# SRAM.net
KiCad netlist of a schematic drawn in Altium Designer
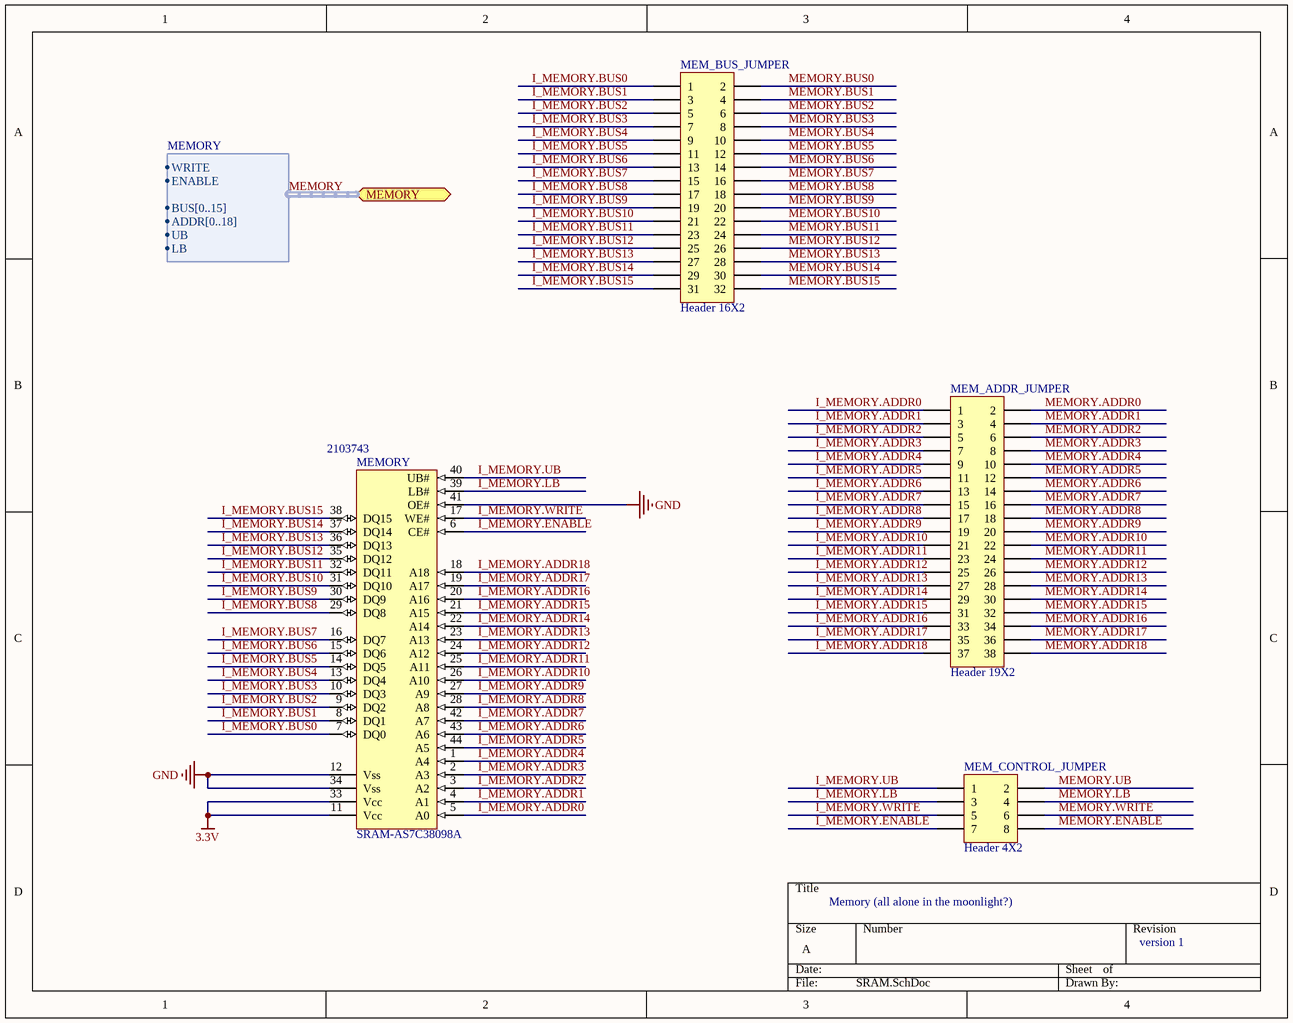
[diagram p0: SRAM.SchDoc]

(export (version "E")
  (design (tool "Eeschema 10.0.6"))
  (components
    (comp (ref "MEMORY")
      (value "SRAM-AS7C38098A")
      (footprint "sram-footprint:AS7C38098A-10TIN")
      (description "ALLIANCE MEMORY - AS7C38098A-10TIN - SRAM, 8MBIT, 512KX16, 3.3V, 44TSOPII")
      (fields
        (field (name "SUPPLIER PART NUMBER 1") "2103743")
        (field (name "MANUFACTURER") "ALLIANCE MEMORY")
        (field (name "MANUFACTURER PART NUMBER") "AS7C38098A-10TIN")
      )
      (libsource (lib "sram-component") (part "memchip-AS7C38098A"))
    )
    (comp (ref "MEM_ADDR_JUMPER")
      (value "Header 19X2")
      (footprint "HDR2X19")
      (description "Header, 19-Pin, Dual row")
      (fields (field (name "PUBLISHER") "Altium Limited"))
      (libsource (lib "Miscellaneous Connectors") (part "Header 19X2"))
    )
    (comp (ref "MEM_BUS_JUMPER")
      (value "Header 16X2")
      (footprint "HDR2X16")
      (description "Header, 16-Pin, Dual row")
      (fields (field (name "PUBLISHER") "Altium Limited"))
      (libsource (lib "Miscellaneous Connectors") (part "Header 16X2"))
    )
    (comp (ref "MEM_CONTROL_JUMPER")
      (value "Header 4X2")
      (footprint "HDR2X4")
      (description "Header, 4-Pin, Dual row")
      (fields (field (name "PUBLISHER") "Altium Limited"))
      (libsource (lib "Miscellaneous Connectors") (part "Header 4X2"))
    )
  )
  (nets
    (net (code "2") (name "/I_MEMORY.ADDR0") (class "Default")
      (node (ref "MEMORY") (pin "5") (pinfunction "A0_5") (pintype "input"))
      (node (ref "MEM_ADDR_JUMPER") (pin "1") (pinfunction "1_1") (pintype "passive"))
    )
    (net (code "3") (name "/I_MEMORY.ADDR1") (class "Default")
      (node (ref "MEMORY") (pin "4") (pinfunction "A1_4") (pintype "input"))
      (node (ref "MEM_ADDR_JUMPER") (pin "3") (pinfunction "3_3") (pintype "passive"))
    )
    (net (code "4") (name "/I_MEMORY.ADDR2") (class "Default")
      (node (ref "MEMORY") (pin "3") (pinfunction "A2_3") (pintype "input"))
      (node (ref "MEM_ADDR_JUMPER") (pin "5") (pinfunction "5_5") (pintype "passive"))
    )
    (net (code "5") (name "/I_MEMORY.ADDR3") (class "Default")
      (node (ref "MEMORY") (pin "2") (pinfunction "A3_2") (pintype "input"))
      (node (ref "MEM_ADDR_JUMPER") (pin "7") (pinfunction "7_7") (pintype "passive"))
    )
    (net (code "6") (name "/I_MEMORY.ADDR4") (class "Default")
      (node (ref "MEMORY") (pin "1") (pinfunction "A4_1") (pintype "input"))
      (node (ref "MEM_ADDR_JUMPER") (pin "9") (pinfunction "9_9") (pintype "passive"))
    )
    (net (code "7") (name "/I_MEMORY.ADDR5") (class "Default")
      (node (ref "MEMORY") (pin "44") (pinfunction "A5_44") (pintype "input"))
      (node (ref "MEM_ADDR_JUMPER") (pin "11") (pinfunction "11_11") (pintype "passive"))
    )
    (net (code "8") (name "/I_MEMORY.ADDR6") (class "Default")
      (node (ref "MEMORY") (pin "43") (pinfunction "A6_43") (pintype "input"))
      (node (ref "MEM_ADDR_JUMPER") (pin "13") (pinfunction "13_13") (pintype "passive"))
    )
    (net (code "9") (name "/I_MEMORY.ADDR7") (class "Default")
      (node (ref "MEMORY") (pin "42") (pinfunction "A7_42") (pintype "input"))
      (node (ref "MEM_ADDR_JUMPER") (pin "15") (pinfunction "15_15") (pintype "passive"))
    )
    (net (code "10") (name "/I_MEMORY.ADDR8") (class "Default")
      (node (ref "MEMORY") (pin "28") (pinfunction "A8_28") (pintype "input"))
      (node (ref "MEM_ADDR_JUMPER") (pin "17") (pinfunction "17_17") (pintype "passive"))
    )
    (net (code "11") (name "/I_MEMORY.ADDR9") (class "Default")
      (node (ref "MEMORY") (pin "27") (pinfunction "A9_27") (pintype "input"))
      (node (ref "MEM_ADDR_JUMPER") (pin "19") (pinfunction "19_19") (pintype "passive"))
    )
    (net (code "12") (name "/I_MEMORY.ADDR10") (class "Default")
      (node (ref "MEMORY") (pin "26") (pinfunction "A10_26") (pintype "input"))
      (node (ref "MEM_ADDR_JUMPER") (pin "21") (pinfunction "21_21") (pintype "passive"))
    )
    (net (code "13") (name "/I_MEMORY.ADDR11") (class "Default")
      (node (ref "MEMORY") (pin "25") (pinfunction "A11_25") (pintype "input"))
      (node (ref "MEM_ADDR_JUMPER") (pin "23") (pinfunction "23_23") (pintype "passive"))
    )
    (net (code "14") (name "/I_MEMORY.ADDR12") (class "Default")
      (node (ref "MEMORY") (pin "24") (pinfunction "A12_24") (pintype "input"))
      (node (ref "MEM_ADDR_JUMPER") (pin "25") (pinfunction "25_25") (pintype "passive"))
    )
    (net (code "15") (name "/I_MEMORY.ADDR13") (class "Default")
      (node (ref "MEMORY") (pin "23") (pinfunction "A13_23") (pintype "input"))
      (node (ref "MEM_ADDR_JUMPER") (pin "27") (pinfunction "27_27") (pintype "passive"))
    )
    (net (code "16") (name "/I_MEMORY.ADDR14") (class "Default")
      (node (ref "MEMORY") (pin "22") (pinfunction "A14_22") (pintype "input"))
      (node (ref "MEM_ADDR_JUMPER") (pin "29") (pinfunction "29_29") (pintype "passive"))
    )
    (net (code "17") (name "/I_MEMORY.ADDR15") (class "Default")
      (node (ref "MEMORY") (pin "21") (pinfunction "A15_21") (pintype "input"))
      (node (ref "MEM_ADDR_JUMPER") (pin "31") (pinfunction "31_31") (pintype "passive"))
    )
    (net (code "18") (name "/I_MEMORY.ADDR16") (class "Default")
      (node (ref "MEMORY") (pin "20") (pinfunction "A16_20") (pintype "input"))
      (node (ref "MEM_ADDR_JUMPER") (pin "33") (pinfunction "33_33") (pintype "passive"))
    )
    (net (code "19") (name "/I_MEMORY.ADDR17") (class "Default")
      (node (ref "MEMORY") (pin "19") (pinfunction "A17_19") (pintype "input"))
      (node (ref "MEM_ADDR_JUMPER") (pin "35") (pinfunction "35_35") (pintype "passive"))
    )
    (net (code "20") (name "/I_MEMORY.ADDR18") (class "Default")
      (node (ref "MEMORY") (pin "18") (pinfunction "A18_18") (pintype "input"))
      (node (ref "MEM_ADDR_JUMPER") (pin "37") (pinfunction "37_37") (pintype "passive"))
    )
    (net (code "21") (name "/I_MEMORY.BUS0") (class "Default")
      (node (ref "MEMORY") (pin "7") (pinfunction "DQ0_7") (pintype "bidirectional"))
      (node (ref "MEM_BUS_JUMPER") (pin "1") (pinfunction "1_1") (pintype "passive"))
    )
    (net (code "22") (name "/I_MEMORY.BUS1") (class "Default")
      (node (ref "MEMORY") (pin "8") (pinfunction "DQ1_8") (pintype "bidirectional"))
      (node (ref "MEM_BUS_JUMPER") (pin "3") (pinfunction "3_3") (pintype "passive"))
    )
    (net (code "23") (name "/I_MEMORY.BUS2") (class "Default")
      (node (ref "MEMORY") (pin "9") (pinfunction "DQ2_9") (pintype "bidirectional"))
      (node (ref "MEM_BUS_JUMPER") (pin "5") (pinfunction "5_5") (pintype "passive"))
    )
    (net (code "24") (name "/I_MEMORY.BUS3") (class "Default")
      (node (ref "MEMORY") (pin "10") (pinfunction "DQ3_10") (pintype "bidirectional"))
      (node (ref "MEM_BUS_JUMPER") (pin "7") (pinfunction "7_7") (pintype "passive"))
    )
    (net (code "25") (name "/I_MEMORY.BUS4") (class "Default")
      (node (ref "MEMORY") (pin "13") (pinfunction "DQ4_13") (pintype "bidirectional"))
      (node (ref "MEM_BUS_JUMPER") (pin "9") (pinfunction "9_9") (pintype "passive"))
    )
    (net (code "26") (name "/I_MEMORY.BUS5") (class "Default")
      (node (ref "MEMORY") (pin "14") (pinfunction "DQ5_14") (pintype "bidirectional"))
      (node (ref "MEM_BUS_JUMPER") (pin "11") (pinfunction "11_11") (pintype "passive"))
    )
    (net (code "27") (name "/I_MEMORY.BUS6") (class "Default")
      (node (ref "MEMORY") (pin "15") (pinfunction "DQ6_15") (pintype "bidirectional"))
      (node (ref "MEM_BUS_JUMPER") (pin "13") (pinfunction "13_13") (pintype "passive"))
    )
    (net (code "28") (name "/I_MEMORY.BUS7") (class "Default")
      (node (ref "MEMORY") (pin "16") (pinfunction "DQ7_16") (pintype "bidirectional"))
      (node (ref "MEM_BUS_JUMPER") (pin "15") (pinfunction "15_15") (pintype "passive"))
    )
    (net (code "29") (name "/I_MEMORY.BUS8") (class "Default")
      (node (ref "MEMORY") (pin "29") (pinfunction "DQ8_29") (pintype "bidirectional"))
      (node (ref "MEM_BUS_JUMPER") (pin "17") (pinfunction "17_17") (pintype "passive"))
    )
    (net (code "30") (name "/I_MEMORY.BUS9") (class "Default")
      (node (ref "MEMORY") (pin "30") (pinfunction "DQ9_30") (pintype "bidirectional"))
      (node (ref "MEM_BUS_JUMPER") (pin "19") (pinfunction "19_19") (pintype "passive"))
    )
    (net (code "31") (name "/I_MEMORY.BUS10") (class "Default")
      (node (ref "MEMORY") (pin "31") (pinfunction "DQ10_31") (pintype "bidirectional"))
      (node (ref "MEM_BUS_JUMPER") (pin "21") (pinfunction "21_21") (pintype "passive"))
    )
    (net (code "32") (name "/I_MEMORY.BUS11") (class "Default")
      (node (ref "MEMORY") (pin "32") (pinfunction "DQ11_32") (pintype "bidirectional"))
      (node (ref "MEM_BUS_JUMPER") (pin "23") (pinfunction "23_23") (pintype "passive"))
    )
    (net (code "33") (name "/I_MEMORY.BUS12") (class "Default")
      (node (ref "MEMORY") (pin "35") (pinfunction "DQ12_35") (pintype "bidirectional"))
      (node (ref "MEM_BUS_JUMPER") (pin "25") (pinfunction "25_25") (pintype "passive"))
    )
    (net (code "34") (name "/I_MEMORY.BUS13") (class "Default")
      (node (ref "MEMORY") (pin "36") (pinfunction "DQ13_36") (pintype "bidirectional"))
      (node (ref "MEM_BUS_JUMPER") (pin "27") (pinfunction "27_27") (pintype "passive"))
    )
    (net (code "35") (name "/I_MEMORY.BUS14") (class "Default")
      (node (ref "MEMORY") (pin "37") (pinfunction "DQ14_37") (pintype "bidirectional"))
      (node (ref "MEM_BUS_JUMPER") (pin "29") (pinfunction "29_29") (pintype "passive"))
    )
    (net (code "36") (name "/I_MEMORY.BUS15") (class "Default")
      (node (ref "MEMORY") (pin "38") (pinfunction "DQ15_38") (pintype "bidirectional"))
      (node (ref "MEM_BUS_JUMPER") (pin "31") (pinfunction "31_31") (pintype "passive"))
    )
    (net (code "37") (name "/I_MEMORY.ENABLE") (class "Default")
      (node (ref "MEMORY") (pin "6") (pinfunction "CE#_6") (pintype "input"))
      (node (ref "MEM_CONTROL_JUMPER") (pin "7") (pinfunction "7_7") (pintype "passive"))
    )
    (net (code "38") (name "/I_MEMORY.LB") (class "Default")
      (node (ref "MEMORY") (pin "39") (pinfunction "LB#_39") (pintype "input"))
      (node (ref "MEM_CONTROL_JUMPER") (pin "3") (pinfunction "3_3") (pintype "passive"))
    )
    (net (code "39") (name "/I_MEMORY.UB") (class "Default")
      (node (ref "MEMORY") (pin "40") (pinfunction "UB#_40") (pintype "input"))
      (node (ref "MEM_CONTROL_JUMPER") (pin "1") (pinfunction "1_1") (pintype "passive"))
    )
    (net (code "40") (name "/I_MEMORY.WRITE") (class "Default")
      (node (ref "MEMORY") (pin "17") (pinfunction "WE#_17") (pintype "input"))
      (node (ref "MEM_CONTROL_JUMPER") (pin "5") (pinfunction "5_5") (pintype "passive"))
    )
    (net (code "41") (name "/MEMORY.ADDR0") (class "Default")
      (node (ref "MEM_ADDR_JUMPER") (pin "2") (pinfunction "2_2") (pintype "passive"))
    )
    (net (code "42") (name "/MEMORY.ADDR1") (class "Default")
      (node (ref "MEM_ADDR_JUMPER") (pin "4") (pinfunction "4_4") (pintype "passive"))
    )
    (net (code "43") (name "/MEMORY.ADDR2") (class "Default")
      (node (ref "MEM_ADDR_JUMPER") (pin "6") (pinfunction "6_6") (pintype "passive"))
    )
    (net (code "44") (name "/MEMORY.ADDR3") (class "Default")
      (node (ref "MEM_ADDR_JUMPER") (pin "8") (pinfunction "8_8") (pintype "passive"))
    )
    (net (code "45") (name "/MEMORY.ADDR4") (class "Default")
      (node (ref "MEM_ADDR_JUMPER") (pin "10") (pinfunction "10_10") (pintype "passive"))
    )
    (net (code "46") (name "/MEMORY.ADDR5") (class "Default")
      (node (ref "MEM_ADDR_JUMPER") (pin "12") (pinfunction "12_12") (pintype "passive"))
    )
    (net (code "47") (name "/MEMORY.ADDR6") (class "Default")
      (node (ref "MEM_ADDR_JUMPER") (pin "14") (pinfunction "14_14") (pintype "passive"))
    )
    (net (code "48") (name "/MEMORY.ADDR7") (class "Default")
      (node (ref "MEM_ADDR_JUMPER") (pin "16") (pinfunction "16_16") (pintype "passive"))
    )
    (net (code "49") (name "/MEMORY.ADDR8") (class "Default")
      (node (ref "MEM_ADDR_JUMPER") (pin "18") (pinfunction "18_18") (pintype "passive"))
    )
    (net (code "50") (name "/MEMORY.ADDR9") (class "Default")
      (node (ref "MEM_ADDR_JUMPER") (pin "20") (pinfunction "20_20") (pintype "passive"))
    )
    (net (code "51") (name "/MEMORY.ADDR10") (class "Default")
      (node (ref "MEM_ADDR_JUMPER") (pin "22") (pinfunction "22_22") (pintype "passive"))
    )
    (net (code "52") (name "/MEMORY.ADDR11") (class "Default")
      (node (ref "MEM_ADDR_JUMPER") (pin "24") (pinfunction "24_24") (pintype "passive"))
    )
    (net (code "53") (name "/MEMORY.ADDR12") (class "Default")
      (node (ref "MEM_ADDR_JUMPER") (pin "26") (pinfunction "26_26") (pintype "passive"))
    )
    (net (code "54") (name "/MEMORY.ADDR13") (class "Default")
      (node (ref "MEM_ADDR_JUMPER") (pin "28") (pinfunction "28_28") (pintype "passive"))
    )
    (net (code "55") (name "/MEMORY.ADDR14") (class "Default")
      (node (ref "MEM_ADDR_JUMPER") (pin "30") (pinfunction "30_30") (pintype "passive"))
    )
    (net (code "56") (name "/MEMORY.ADDR15") (class "Default")
      (node (ref "MEM_ADDR_JUMPER") (pin "32") (pinfunction "32_32") (pintype "passive"))
    )
    (net (code "57") (name "/MEMORY.ADDR16") (class "Default")
      (node (ref "MEM_ADDR_JUMPER") (pin "34") (pinfunction "34_34") (pintype "passive"))
    )
    (net (code "58") (name "/MEMORY.ADDR17") (class "Default")
      (node (ref "MEM_ADDR_JUMPER") (pin "36") (pinfunction "36_36") (pintype "passive"))
    )
    (net (code "59") (name "/MEMORY.ADDR18") (class "Default")
      (node (ref "MEM_ADDR_JUMPER") (pin "38") (pinfunction "38_38") (pintype "passive"))
    )
    (net (code "60") (name "/MEMORY.BUS0") (class "Default")
      (node (ref "MEM_BUS_JUMPER") (pin "2") (pinfunction "2_2") (pintype "passive"))
    )
    (net (code "61") (name "/MEMORY.BUS1") (class "Default")
      (node (ref "MEM_BUS_JUMPER") (pin "4") (pinfunction "4_4") (pintype "passive"))
    )
    (net (code "62") (name "/MEMORY.BUS2") (class "Default")
      (node (ref "MEM_BUS_JUMPER") (pin "6") (pinfunction "6_6") (pintype "passive"))
    )
    (net (code "63") (name "/MEMORY.BUS3") (class "Default")
      (node (ref "MEM_BUS_JUMPER") (pin "8") (pinfunction "8_8") (pintype "passive"))
    )
    (net (code "64") (name "/MEMORY.BUS4") (class "Default")
      (node (ref "MEM_BUS_JUMPER") (pin "10") (pinfunction "10_10") (pintype "passive"))
    )
    (net (code "65") (name "/MEMORY.BUS5") (class "Default")
      (node (ref "MEM_BUS_JUMPER") (pin "12") (pinfunction "12_12") (pintype "passive"))
    )
    (net (code "66") (name "/MEMORY.BUS6") (class "Default")
      (node (ref "MEM_BUS_JUMPER") (pin "14") (pinfunction "14_14") (pintype "passive"))
    )
    (net (code "67") (name "/MEMORY.BUS7") (class "Default")
      (node (ref "MEM_BUS_JUMPER") (pin "16") (pinfunction "16_16") (pintype "passive"))
    )
    (net (code "68") (name "/MEMORY.BUS8") (class "Default")
      (node (ref "MEM_BUS_JUMPER") (pin "18") (pinfunction "18_18") (pintype "passive"))
    )
    (net (code "69") (name "/MEMORY.BUS9") (class "Default")
      (node (ref "MEM_BUS_JUMPER") (pin "20") (pinfunction "20_20") (pintype "passive"))
    )
    (net (code "70") (name "/MEMORY.BUS10") (class "Default")
      (node (ref "MEM_BUS_JUMPER") (pin "22") (pinfunction "22_22") (pintype "passive"))
    )
    (net (code "71") (name "/MEMORY.BUS11") (class "Default")
      (node (ref "MEM_BUS_JUMPER") (pin "24") (pinfunction "24_24") (pintype "passive"))
    )
    (net (code "72") (name "/MEMORY.BUS12") (class "Default")
      (node (ref "MEM_BUS_JUMPER") (pin "26") (pinfunction "26_26") (pintype "passive"))
    )
    (net (code "73") (name "/MEMORY.BUS13") (class "Default")
      (node (ref "MEM_BUS_JUMPER") (pin "28") (pinfunction "28_28") (pintype "passive"))
    )
    (net (code "74") (name "/MEMORY.BUS14") (class "Default")
      (node (ref "MEM_BUS_JUMPER") (pin "30") (pinfunction "30_30") (pintype "passive"))
    )
    (net (code "75") (name "/MEMORY.BUS15") (class "Default")
      (node (ref "MEM_BUS_JUMPER") (pin "32") (pinfunction "32_32") (pintype "passive"))
    )
    (net (code "76") (name "/MEMORY.ENABLE") (class "Default")
      (node (ref "MEM_CONTROL_JUMPER") (pin "8") (pinfunction "8_8") (pintype "passive"))
    )
    (net (code "77") (name "/MEMORY.LB") (class "Default")
      (node (ref "MEM_CONTROL_JUMPER") (pin "4") (pinfunction "4_4") (pintype "passive"))
    )
    (net (code "78") (name "/MEMORY.UB") (class "Default")
      (node (ref "MEM_CONTROL_JUMPER") (pin "2") (pinfunction "2_2") (pintype "passive"))
    )
    (net (code "79") (name "/MEMORY.WRITE") (class "Default")
      (node (ref "MEM_CONTROL_JUMPER") (pin "6") (pinfunction "6_6") (pintype "passive"))
    )
    (net (code "81") (name "3.3V") (class "Default")
      (node (ref "MEMORY") (pin "11") (pinfunction "Vcc_11") (pintype "power_in"))
      (node (ref "MEMORY") (pin "33") (pinfunction "Vcc_33") (pintype "power_in"))
    )
    (net (code "82") (name "GND") (class "Default")
      (node (ref "MEMORY") (pin "12") (pinfunction "Vss_12") (pintype "power_in"))
      (node (ref "MEMORY") (pin "34") (pinfunction "Vss_34") (pintype "power_in"))
      (node (ref "MEMORY") (pin "41") (pinfunction "OE#_41") (pintype "input"))
    )
  )
)
